# radioboard.net
KiCad netlist of a schematic drawn in EAGLE
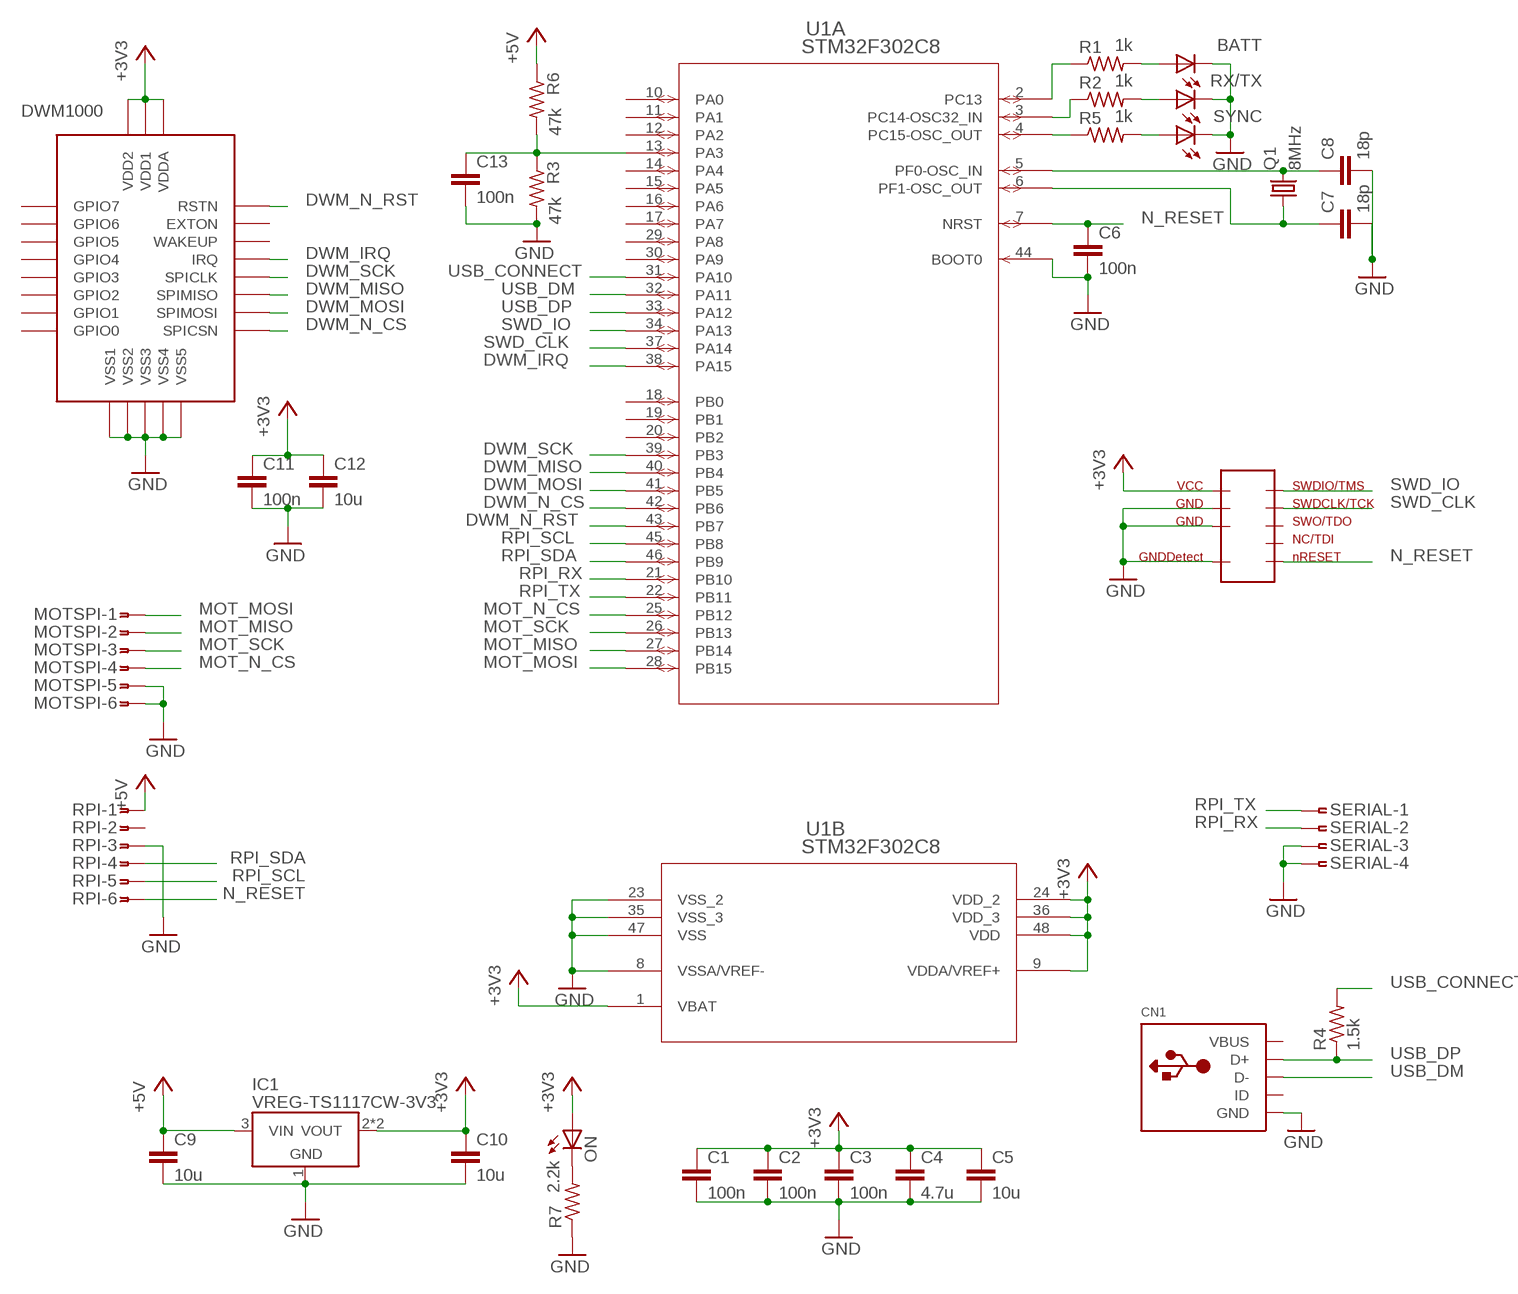
[diagram p0: schematic, sheet 1]

(export (version "E")
  (design (tool "Eeschema 10.0.6"))
  (components
    (comp (ref "BATT")
      (value "LEDCHIPLED_0805")
      (footprint "eagle-import:CHIPLED_0805")
      (libsource (lib "eagle-import") (part "LEDCHIPLED_0805"))
    )
    (comp (ref "C1")
      (value "100n")
      (footprint "eagle-import:C0805")
      (libsource (lib "eagle-import") (part "C-EUC0805"))
    )
    (comp (ref "C2")
      (value "100n")
      (footprint "eagle-import:C0805")
      (libsource (lib "eagle-import") (part "C-EUC0805"))
    )
    (comp (ref "C3")
      (value "100n")
      (footprint "eagle-import:C0805")
      (libsource (lib "eagle-import") (part "C-EUC0805"))
    )
    (comp (ref "C4")
      (value "4.7u")
      (footprint "eagle-import:C0805")
      (libsource (lib "eagle-import") (part "C-EUC0805"))
    )
    (comp (ref "C5")
      (value "10u")
      (footprint "eagle-import:C0805")
      (libsource (lib "eagle-import") (part "C-EUC0805"))
    )
    (comp (ref "C6")
      (value "100n")
      (footprint "eagle-import:C0805")
      (libsource (lib "eagle-import") (part "C-EUC0805"))
    )
    (comp (ref "C7")
      (value "18p")
      (footprint "eagle-import:C0805")
      (libsource (lib "eagle-import") (part "C-EUC0805"))
    )
    (comp (ref "C8")
      (value "18p")
      (footprint "eagle-import:C0805")
      (libsource (lib "eagle-import") (part "C-EUC0805"))
    )
    (comp (ref "C9")
      (value "10u")
      (footprint "eagle-import:C0805")
      (libsource (lib "eagle-import") (part "C-EUC0805"))
    )
    (comp (ref "C10")
      (value "10u")
      (footprint "eagle-import:C0805")
      (libsource (lib "eagle-import") (part "C-EUC0805"))
    )
    (comp (ref "C11")
      (value "100n")
      (footprint "eagle-import:C0805")
      (libsource (lib "eagle-import") (part "C-EUC0805"))
    )
    (comp (ref "C12")
      (value "10u")
      (footprint "eagle-import:C0805")
      (libsource (lib "eagle-import") (part "C-EUC0805"))
    )
    (comp (ref "C13")
      (value "100n")
      (footprint "eagle-import:C0805")
      (libsource (lib "eagle-import") (part "C-EUC0805"))
    )
    (comp (ref "CN1")
      (value "USBMINIB")
      (footprint "eagle-import:USB-MINIB")
      (libsource (lib "eagle-import") (part "USBMINIB"))
    )
    (comp (ref "DWM1000")
      (value "DWM1000")
      (footprint "eagle-import:DW1000-PACKAGE")
      (libsource (lib "eagle-import") (part "DWM1000"))
    )
    (comp (ref "IC1")
      (value "VREG-TS1117CW-3V3")
      (footprint "eagle-import:SOT223")
      (libsource (lib "eagle-import") (part "VREG-TS1117CW-3V3"))
    )
    (comp (ref "MOTSPI")
      (value "SMDTOP-6")
      (footprint "eagle-import:SMDTOP6")
      (libsource (lib "eagle-import") (part "SMDTOP-6"))
    )
    (comp (ref "ON")
      (value "LEDCHIPLED_0805")
      (footprint "eagle-import:CHIPLED_0805")
      (libsource (lib "eagle-import") (part "LEDCHIPLED_0805"))
    )
    (comp (ref "Q1")
      (value "8MHz")
      (footprint "eagle-import:SM49")
      (libsource (lib "eagle-import") (part "CRYSTALSM49"))
    )
    (comp (ref "R1")
      (value "1k")
      (footprint "eagle-import:M0805")
      (libsource (lib "eagle-import") (part "R-US_M0805"))
    )
    (comp (ref "R2")
      (value "1k")
      (footprint "eagle-import:M0805")
      (libsource (lib "eagle-import") (part "R-US_M0805"))
    )
    (comp (ref "R3")
      (value "47k")
      (footprint "eagle-import:M0805")
      (libsource (lib "eagle-import") (part "R-US_M0805"))
    )
    (comp (ref "R4")
      (value "1.5k")
      (footprint "eagle-import:M0805")
      (libsource (lib "eagle-import") (part "R-US_M0805"))
    )
    (comp (ref "R5")
      (value "1k")
      (footprint "eagle-import:M0805")
      (libsource (lib "eagle-import") (part "R-US_M0805"))
    )
    (comp (ref "R6")
      (value "47k")
      (footprint "eagle-import:M0805")
      (libsource (lib "eagle-import") (part "R-US_M0805"))
    )
    (comp (ref "R7")
      (value "2.2k")
      (footprint "eagle-import:M0805")
      (libsource (lib "eagle-import") (part "R-US_M0805"))
    )
    (comp (ref "RPI")
      (value "SMDTOP-6")
      (footprint "eagle-import:SMDTOP6")
      (libsource (lib "eagle-import") (part "SMDTOP-6"))
    )
    (comp (ref "RX/TX")
      (value "LEDCHIPLED_0805")
      (footprint "eagle-import:CHIPLED_0805")
      (libsource (lib "eagle-import") (part "LEDCHIPLED_0805"))
    )
    (comp (ref "SERIAL")
      (value "SMDTOP-4")
      (footprint "eagle-import:SMDTOP4")
      (libsource (lib "eagle-import") (part "SMDTOP-4"))
    )
    (comp (ref "SYNC")
      (value "LEDCHIPLED_0805")
      (footprint "eagle-import:CHIPLED_0805")
      (libsource (lib "eagle-import") (part "LEDCHIPLED_0805"))
    )
    (comp (ref "U$1")
      (value "SWD/JTAG-_PINS")
      (footprint "eagle-import:SAMTEC_SHF-105-01-L-D-SM")
      (libsource (lib "eagle-import") (part "SWD/JTAG-_PINS"))
    )
    (comp (ref "U1")
      (value "STM32F302C8")
      (footprint "eagle-import:LQFP48-7X7MM")
      (fields
        (field (name "MANUFACTURER_PART_NUMBER") "stm32f302_303c2")
        (field (name "COPYRIGHT") "Copyright C 2016 Accelerated Designs. All rights reserved")
      )
      (libsource (lib "eagle-import") (part "STM32F302_303C2"))
    )
  )
  (nets
    (net (code "1") (name "+3V3") (class "Default")
      (node (ref "C1") (pin "1") (pinfunction "1_1") (pintype "passive"))
      (node (ref "C10") (pin "1") (pinfunction "1_1") (pintype "passive"))
      (node (ref "C11") (pin "1") (pinfunction "1_1") (pintype "passive"))
      (node (ref "C12") (pin "1") (pinfunction "1_1") (pintype "passive"))
      (node (ref "C2") (pin "1") (pinfunction "1_1") (pintype "passive"))
      (node (ref "C3") (pin "1") (pinfunction "1_1") (pintype "passive"))
      (node (ref "C4") (pin "1") (pinfunction "1_1") (pintype "passive"))
      (node (ref "C5") (pin "1") (pinfunction "1_1") (pintype "passive"))
      (node (ref "DWM1000") (pin "VDD3V3") (pinfunction "VDD1_VDD3V3") (pintype "power_in"))
      (node (ref "DWM1000") (pin "VDD3V32") (pinfunction "VDD2_VDD3V32") (pintype "power_in"))
      (node (ref "DWM1000") (pin "VDDAON") (pinfunction "VDDA_VDDAON") (pintype "power_in"))
      (node (ref "IC1") (pin "2") (pinfunction "VOUT_2") (pintype "power_in"))
      (node (ref "IC1") (pin "4") (pinfunction "VOUT_4") (pintype "power_in"))
      (node (ref "ON") (pin "A") (pinfunction "A_A") (pintype "passive"))
      (node (ref "U$1") (pin "P$1") (pinfunction "P$1_P$1") (pintype "bidirectional"))
      (node (ref "U1") (pin "1") (pinfunction "VBAT_1") (pintype "power_in"))
      (node (ref "U1") (pin "24") (pinfunction "VDD_2_24") (pintype "power_in"))
      (node (ref "U1") (pin "36") (pinfunction "VDD_3_36") (pintype "power_in"))
      (node (ref "U1") (pin "48") (pinfunction "VDD_48") (pintype "power_in"))
      (node (ref "U1") (pin "9") (pinfunction "VDDA/VREF+_9") (pintype "power_in"))
    )
    (net (code "2") (name "+5V") (class "Default")
      (node (ref "C9") (pin "1") (pinfunction "1_1") (pintype "passive"))
      (node (ref "IC1") (pin "3") (pinfunction "VIN_3") (pintype "power_in"))
      (node (ref "R6") (pin "1") (pinfunction "1_1") (pintype "passive"))
      (node (ref "RPI") (pin "1") (pinfunction "1_1") (pintype "passive"))
    )
    (net (code "3") (name "/DWM_IRQ") (class "Default")
      (node (ref "DWM1000") (pin "IRQ") (pinfunction "IRQ_IRQ") (pintype "bidirectional"))
      (node (ref "U1") (pin "38") (pinfunction "PA15_38") (pintype "bidirectional"))
    )
    (net (code "4") (name "/DWM_MISO") (class "Default")
      (node (ref "DWM1000") (pin "SPIMISO") (pinfunction "SPIMISO_SPIMISO") (pintype "bidirectional"))
      (node (ref "U1") (pin "40") (pinfunction "PB4_40") (pintype "bidirectional"))
    )
    (net (code "5") (name "/DWM_MOSI") (class "Default")
      (node (ref "DWM1000") (pin "SPIMOSI") (pinfunction "SPIMOSI_SPIMOSI") (pintype "bidirectional"))
      (node (ref "U1") (pin "41") (pinfunction "PB5_41") (pintype "bidirectional"))
    )
    (net (code "6") (name "/DWM_N_CS") (class "Default")
      (node (ref "DWM1000") (pin "SPICSN") (pinfunction "SPICSN_SPICSN") (pintype "bidirectional"))
      (node (ref "U1") (pin "42") (pinfunction "PB6_42") (pintype "bidirectional"))
    )
    (net (code "7") (name "/DWM_N_RST") (class "Default")
      (node (ref "DWM1000") (pin "RSTN") (pinfunction "RSTN_RSTN") (pintype "bidirectional"))
      (node (ref "U1") (pin "43") (pinfunction "PB7_43") (pintype "bidirectional"))
    )
    (net (code "8") (name "/DWM_SCK") (class "Default")
      (node (ref "DWM1000") (pin "SPICLK") (pinfunction "SPICLK_SPICLK") (pintype "bidirectional"))
      (node (ref "U1") (pin "39") (pinfunction "PB3_39") (pintype "bidirectional"))
    )
    (net (code "9") (name "/MOT_MISO") (class "Default")
      (node (ref "MOTSPI") (pin "2") (pinfunction "1_2") (pintype "passive"))
      (node (ref "U1") (pin "27") (pinfunction "PB14_27") (pintype "bidirectional"))
    )
    (net (code "10") (name "/MOT_MOSI") (class "Default")
      (node (ref "MOTSPI") (pin "1") (pinfunction "1_1") (pintype "passive"))
      (node (ref "U1") (pin "28") (pinfunction "PB15_28") (pintype "bidirectional"))
    )
    (net (code "11") (name "/MOT_N_CS") (class "Default")
      (node (ref "MOTSPI") (pin "4") (pinfunction "1_4") (pintype "passive"))
      (node (ref "U1") (pin "25") (pinfunction "PB12_25") (pintype "bidirectional"))
    )
    (net (code "12") (name "/MOT_SCK") (class "Default")
      (node (ref "MOTSPI") (pin "3") (pinfunction "1_3") (pintype "passive"))
      (node (ref "U1") (pin "26") (pinfunction "PB13_26") (pintype "bidirectional"))
    )
    (net (code "13") (name "/N_RESET") (class "Default")
      (node (ref "C6") (pin "1") (pinfunction "1_1") (pintype "passive"))
      (node (ref "RPI") (pin "6") (pinfunction "1_6") (pintype "passive"))
      (node (ref "U$1") (pin "P$10") (pinfunction "P$10_P$10") (pintype "bidirectional"))
      (node (ref "U1") (pin "7") (pinfunction "NRST_7") (pintype "bidirectional"))
    )
    (net (code "14") (name "/RPI_RX") (class "Default")
      (node (ref "SERIAL") (pin "2") (pinfunction "1_2") (pintype "passive"))
      (node (ref "U1") (pin "21") (pinfunction "PB10_21") (pintype "bidirectional"))
    )
    (net (code "15") (name "/RPI_SCL") (class "Default")
      (node (ref "RPI") (pin "5") (pinfunction "1_5") (pintype "passive"))
      (node (ref "U1") (pin "45") (pinfunction "PB8_45") (pintype "bidirectional"))
    )
    (net (code "16") (name "/RPI_SDA") (class "Default")
      (node (ref "RPI") (pin "4") (pinfunction "1_4") (pintype "passive"))
      (node (ref "U1") (pin "46") (pinfunction "PB9_46") (pintype "bidirectional"))
    )
    (net (code "17") (name "/RPI_TX") (class "Default")
      (node (ref "SERIAL") (pin "1") (pinfunction "1_1") (pintype "passive"))
      (node (ref "U1") (pin "22") (pinfunction "PB11_22") (pintype "bidirectional"))
    )
    (net (code "18") (name "/SWD_CLK") (class "Default")
      (node (ref "U$1") (pin "P$4") (pinfunction "P$4_P$4") (pintype "bidirectional"))
      (node (ref "U1") (pin "37") (pinfunction "PA14_37") (pintype "bidirectional"))
    )
    (net (code "19") (name "/SWD_IO") (class "Default")
      (node (ref "U$1") (pin "P$2") (pinfunction "P$2_P$2") (pintype "bidirectional"))
      (node (ref "U1") (pin "34") (pinfunction "PA13_34") (pintype "bidirectional"))
    )
    (net (code "20") (name "/USB_CONNECT") (class "Default")
      (node (ref "R4") (pin "2") (pinfunction "2_2") (pintype "passive"))
      (node (ref "U1") (pin "31") (pinfunction "PA10_31") (pintype "bidirectional"))
    )
    (net (code "21") (name "/USB_DM") (class "Default")
      (node (ref "CN1") (pin "D-") (pinfunction "D-_D-") (pintype "bidirectional"))
      (node (ref "U1") (pin "32") (pinfunction "PA11_32") (pintype "bidirectional"))
    )
    (net (code "22") (name "/USB_DP") (class "Default")
      (node (ref "CN1") (pin "D+") (pinfunction "D+_D+") (pintype "bidirectional"))
      (node (ref "R4") (pin "1") (pinfunction "1_1") (pintype "passive"))
      (node (ref "U1") (pin "33") (pinfunction "PA12_33") (pintype "bidirectional"))
    )
    (net (code "23") (name "/VBUS") (class "Default")
      (node (ref "CN1") (pin "VBUS") (pinfunction "VBUS_VBUS") (pintype "power_in"))
    )
    (net (code "24") (name "GND") (class "Default")
      (node (ref "BATT") (pin "C") (pinfunction "C_C") (pintype "passive"))
      (node (ref "C1") (pin "2") (pinfunction "2_2") (pintype "passive"))
      (node (ref "C10") (pin "2") (pinfunction "2_2") (pintype "passive"))
      (node (ref "C11") (pin "2") (pinfunction "2_2") (pintype "passive"))
      (node (ref "C12") (pin "2") (pinfunction "2_2") (pintype "passive"))
      (node (ref "C13") (pin "2") (pinfunction "2_2") (pintype "passive"))
      (node (ref "C2") (pin "2") (pinfunction "2_2") (pintype "passive"))
      (node (ref "C3") (pin "2") (pinfunction "2_2") (pintype "passive"))
      (node (ref "C4") (pin "2") (pinfunction "2_2") (pintype "passive"))
      (node (ref "C5") (pin "2") (pinfunction "2_2") (pintype "passive"))
      (node (ref "C6") (pin "2") (pinfunction "2_2") (pintype "passive"))
      (node (ref "C7") (pin "2") (pinfunction "2_2") (pintype "passive"))
      (node (ref "C8") (pin "2") (pinfunction "2_2") (pintype "passive"))
      (node (ref "C9") (pin "2") (pinfunction "2_2") (pintype "passive"))
      (node (ref "CN1") (pin "GND") (pinfunction "GND_GND") (pintype "power_in"))
      (node (ref "DWM1000") (pin "VSS1") (pinfunction "VSS1_VSS1") (pintype "power_in"))
      (node (ref "DWM1000") (pin "VSS2") (pinfunction "VSS2_VSS2") (pintype "power_in"))
      (node (ref "DWM1000") (pin "VSS3") (pinfunction "VSS3_VSS3") (pintype "power_in"))
      (node (ref "DWM1000") (pin "VSS4") (pinfunction "VSS4_VSS4") (pintype "power_in"))
      (node (ref "DWM1000") (pin "VSS5") (pinfunction "VSS5_VSS5") (pintype "power_in"))
      (node (ref "IC1") (pin "1") (pinfunction "GND_1") (pintype "power_in"))
      (node (ref "MOTSPI") (pin "5") (pinfunction "1_5") (pintype "passive"))
      (node (ref "MOTSPI") (pin "6") (pinfunction "1_6") (pintype "passive"))
      (node (ref "R3") (pin "2") (pinfunction "2_2") (pintype "passive"))
      (node (ref "R7") (pin "1") (pinfunction "1_1") (pintype "passive"))
      (node (ref "RPI") (pin "3") (pinfunction "1_3") (pintype "passive"))
      (node (ref "RX/TX") (pin "C") (pinfunction "C_C") (pintype "passive"))
      (node (ref "SERIAL") (pin "3") (pinfunction "1_3") (pintype "passive"))
      (node (ref "SERIAL") (pin "4") (pinfunction "1_4") (pintype "passive"))
      (node (ref "SYNC") (pin "C") (pinfunction "C_C") (pintype "passive"))
      (node (ref "U$1") (pin "P$3") (pinfunction "P$3_P$3") (pintype "bidirectional"))
      (node (ref "U$1") (pin "P$5") (pinfunction "P$5_P$5") (pintype "bidirectional"))
      (node (ref "U$1") (pin "P$9") (pinfunction "P$9_P$9") (pintype "bidirectional"))
      (node (ref "U1") (pin "23") (pinfunction "VSS_2_23") (pintype "power_in"))
      (node (ref "U1") (pin "35") (pinfunction "VSS_3_35") (pintype "power_in"))
      (node (ref "U1") (pin "44") (pinfunction "BOOT0_44") (pintype "input"))
      (node (ref "U1") (pin "47") (pinfunction "VSS_47") (pintype "power_in"))
      (node (ref "U1") (pin "8") (pinfunction "VSSA/VREF-_8") (pintype "power_in"))
    )
    (net (code "25") (name "Net-(BATT-PadA)") (class "Default")
      (node (ref "BATT") (pin "A") (pinfunction "A_A") (pintype "passive"))
      (node (ref "R1") (pin "2") (pinfunction "2_2") (pintype "passive"))
    )
    (net (code "26") (name "Net-(ON-PadC)") (class "Default")
      (node (ref "ON") (pin "C") (pinfunction "C_C") (pintype "passive"))
      (node (ref "R7") (pin "2") (pinfunction "2_2") (pintype "passive"))
    )
    (net (code "27") (name "Net-(R2-Pad2)") (class "Default")
      (node (ref "R2") (pin "2") (pinfunction "2_2") (pintype "passive"))
      (node (ref "RX/TX") (pin "A") (pinfunction "A_A") (pintype "passive"))
    )
    (net (code "28") (name "Net-(R5-Pad2)") (class "Default")
      (node (ref "R5") (pin "2") (pinfunction "2_2") (pintype "passive"))
      (node (ref "SYNC") (pin "A") (pinfunction "A_A") (pintype "passive"))
    )
    (net (code "29") (name "Net-(U1A-PA3)") (class "Default")
      (node (ref "C13") (pin "1") (pinfunction "1_1") (pintype "passive"))
      (node (ref "R3") (pin "1") (pinfunction "1_1") (pintype "passive"))
      (node (ref "R6") (pin "2") (pinfunction "2_2") (pintype "passive"))
      (node (ref "U1") (pin "13") (pinfunction "PA3_13") (pintype "bidirectional"))
    )
    (net (code "30") (name "Net-(U1A-PC13)") (class "Default")
      (node (ref "R1") (pin "1") (pinfunction "1_1") (pintype "passive"))
      (node (ref "U1") (pin "2") (pinfunction "PC13_2") (pintype "bidirectional"))
    )
    (net (code "31") (name "Net-(U1A-PC14-OSC32_IN)") (class "Default")
      (node (ref "R2") (pin "1") (pinfunction "1_1") (pintype "passive"))
      (node (ref "U1") (pin "3") (pinfunction "PC14-OSC32_IN_3") (pintype "bidirectional"))
    )
    (net (code "32") (name "Net-(U1A-PC15-OSC_OUT)") (class "Default")
      (node (ref "R5") (pin "1") (pinfunction "1_1") (pintype "passive"))
      (node (ref "U1") (pin "4") (pinfunction "PC15-OSC_OUT_4") (pintype "bidirectional"))
    )
    (net (code "33") (name "Net-(U1A-PF0-OSC_IN)") (class "Default")
      (node (ref "C8") (pin "1") (pinfunction "1_1") (pintype "passive"))
      (node (ref "Q1") (pin "2") (pinfunction "2_2") (pintype "passive"))
      (node (ref "U1") (pin "5") (pinfunction "PF0-OSC_IN_5") (pintype "bidirectional"))
    )
    (net (code "34") (name "Net-(U1A-PF1-OSC_OUT)") (class "Default")
      (node (ref "C7") (pin "1") (pinfunction "1_1") (pintype "passive"))
      (node (ref "Q1") (pin "1") (pinfunction "1_1") (pintype "passive"))
      (node (ref "U1") (pin "6") (pinfunction "PF1-OSC_OUT_6") (pintype "bidirectional"))
    )
    (net (code "35") (name "unconnected-(CN1-PadID)") (class "Default")
      (node (ref "CN1") (pin "ID") (pinfunction "ID_ID") (pintype "bidirectional"))
    )
    (net (code "36") (name "unconnected-(DWM1000-PadEXTON)") (class "Default")
      (node (ref "DWM1000") (pin "EXTON") (pinfunction "EXTON_EXTON") (pintype "bidirectional"))
    )
    (net (code "37") (name "unconnected-(DWM1000-PadGPIO0)") (class "Default")
      (node (ref "DWM1000") (pin "GPIO0") (pinfunction "GPIO0_GPIO0") (pintype "bidirectional"))
    )
    (net (code "38") (name "unconnected-(DWM1000-PadGPIO1)") (class "Default")
      (node (ref "DWM1000") (pin "GPIO1") (pinfunction "GPIO1_GPIO1") (pintype "bidirectional"))
    )
    (net (code "39") (name "unconnected-(DWM1000-PadGPIO2)") (class "Default")
      (node (ref "DWM1000") (pin "GPIO2") (pinfunction "GPIO2_GPIO2") (pintype "bidirectional"))
    )
    (net (code "40") (name "unconnected-(DWM1000-PadGPIO3)") (class "Default")
      (node (ref "DWM1000") (pin "GPIO3") (pinfunction "GPIO3_GPIO3") (pintype "bidirectional"))
    )
    (net (code "41") (name "unconnected-(DWM1000-PadGPIO4)") (class "Default")
      (node (ref "DWM1000") (pin "GPIO4") (pinfunction "GPIO4_GPIO4") (pintype "bidirectional"))
    )
    (net (code "42") (name "unconnected-(DWM1000-PadGPIO5)") (class "Default")
      (node (ref "DWM1000") (pin "GPIO5") (pinfunction "GPIO5_GPIO5") (pintype "bidirectional"))
    )
    (net (code "43") (name "unconnected-(DWM1000-PadGPIO6)") (class "Default")
      (node (ref "DWM1000") (pin "GPIO6") (pinfunction "GPIO6_GPIO6") (pintype "bidirectional"))
    )
    (net (code "44") (name "unconnected-(DWM1000-PadGPIO7)") (class "Default")
      (node (ref "DWM1000") (pin "GPIO7") (pinfunction "GPIO7_GPIO7") (pintype "bidirectional"))
    )
    (net (code "45") (name "unconnected-(DWM1000-PadWAKEUP)") (class "Default")
      (node (ref "DWM1000") (pin "WAKEUP") (pinfunction "WAKEUP_WAKEUP") (pintype "bidirectional"))
    )
    (net (code "46") (name "unconnected-(RPIB-1-Pad2)") (class "Default")
      (node (ref "RPI") (pin "2") (pinfunction "1_2") (pintype "passive"))
    )
    (net (code "47") (name "unconnected-(U$1-PadP$6)") (class "Default")
      (node (ref "U$1") (pin "P$6") (pinfunction "P$6_P$6") (pintype "bidirectional"))
    )
    (net (code "48") (name "unconnected-(U$1-PadP$8)") (class "Default")
      (node (ref "U$1") (pin "P$8") (pinfunction "P$8_P$8") (pintype "bidirectional"))
    )
    (net (code "49") (name "unconnected-(U1A-PA0-Pad10)") (class "Default")
      (node (ref "U1") (pin "10") (pinfunction "PA0_10") (pintype "bidirectional"))
    )
    (net (code "50") (name "unconnected-(U1A-PA1-Pad11)") (class "Default")
      (node (ref "U1") (pin "11") (pinfunction "PA1_11") (pintype "bidirectional"))
    )
    (net (code "51") (name "unconnected-(U1A-PA2-Pad12)") (class "Default")
      (node (ref "U1") (pin "12") (pinfunction "PA2_12") (pintype "bidirectional"))
    )
    (net (code "52") (name "unconnected-(U1A-PA4-Pad14)") (class "Default")
      (node (ref "U1") (pin "14") (pinfunction "PA4_14") (pintype "bidirectional"))
    )
    (net (code "53") (name "unconnected-(U1A-PA5-Pad15)") (class "Default")
      (node (ref "U1") (pin "15") (pinfunction "PA5_15") (pintype "bidirectional"))
    )
    (net (code "54") (name "unconnected-(U1A-PA6-Pad16)") (class "Default")
      (node (ref "U1") (pin "16") (pinfunction "PA6_16") (pintype "bidirectional"))
    )
    (net (code "55") (name "unconnected-(U1A-PA7-Pad17)") (class "Default")
      (node (ref "U1") (pin "17") (pinfunction "PA7_17") (pintype "bidirectional"))
    )
    (net (code "56") (name "unconnected-(U1A-PA8-Pad29)") (class "Default")
      (node (ref "U1") (pin "29") (pinfunction "PA8_29") (pintype "bidirectional"))
    )
    (net (code "57") (name "unconnected-(U1A-PA9-Pad30)") (class "Default")
      (node (ref "U1") (pin "30") (pinfunction "PA9_30") (pintype "bidirectional"))
    )
    (net (code "58") (name "unconnected-(U1A-PB0-Pad18)") (class "Default")
      (node (ref "U1") (pin "18") (pinfunction "PB0_18") (pintype "bidirectional"))
    )
    (net (code "59") (name "unconnected-(U1A-PB1-Pad19)") (class "Default")
      (node (ref "U1") (pin "19") (pinfunction "PB1_19") (pintype "bidirectional"))
    )
    (net (code "60") (name "unconnected-(U1A-PB2-Pad20)") (class "Default")
      (node (ref "U1") (pin "20") (pinfunction "PB2_20") (pintype "bidirectional"))
    )
  )
)
